# ESP32-WROOM.net
KiCad netlist of a schematic drawn in Altium Designer
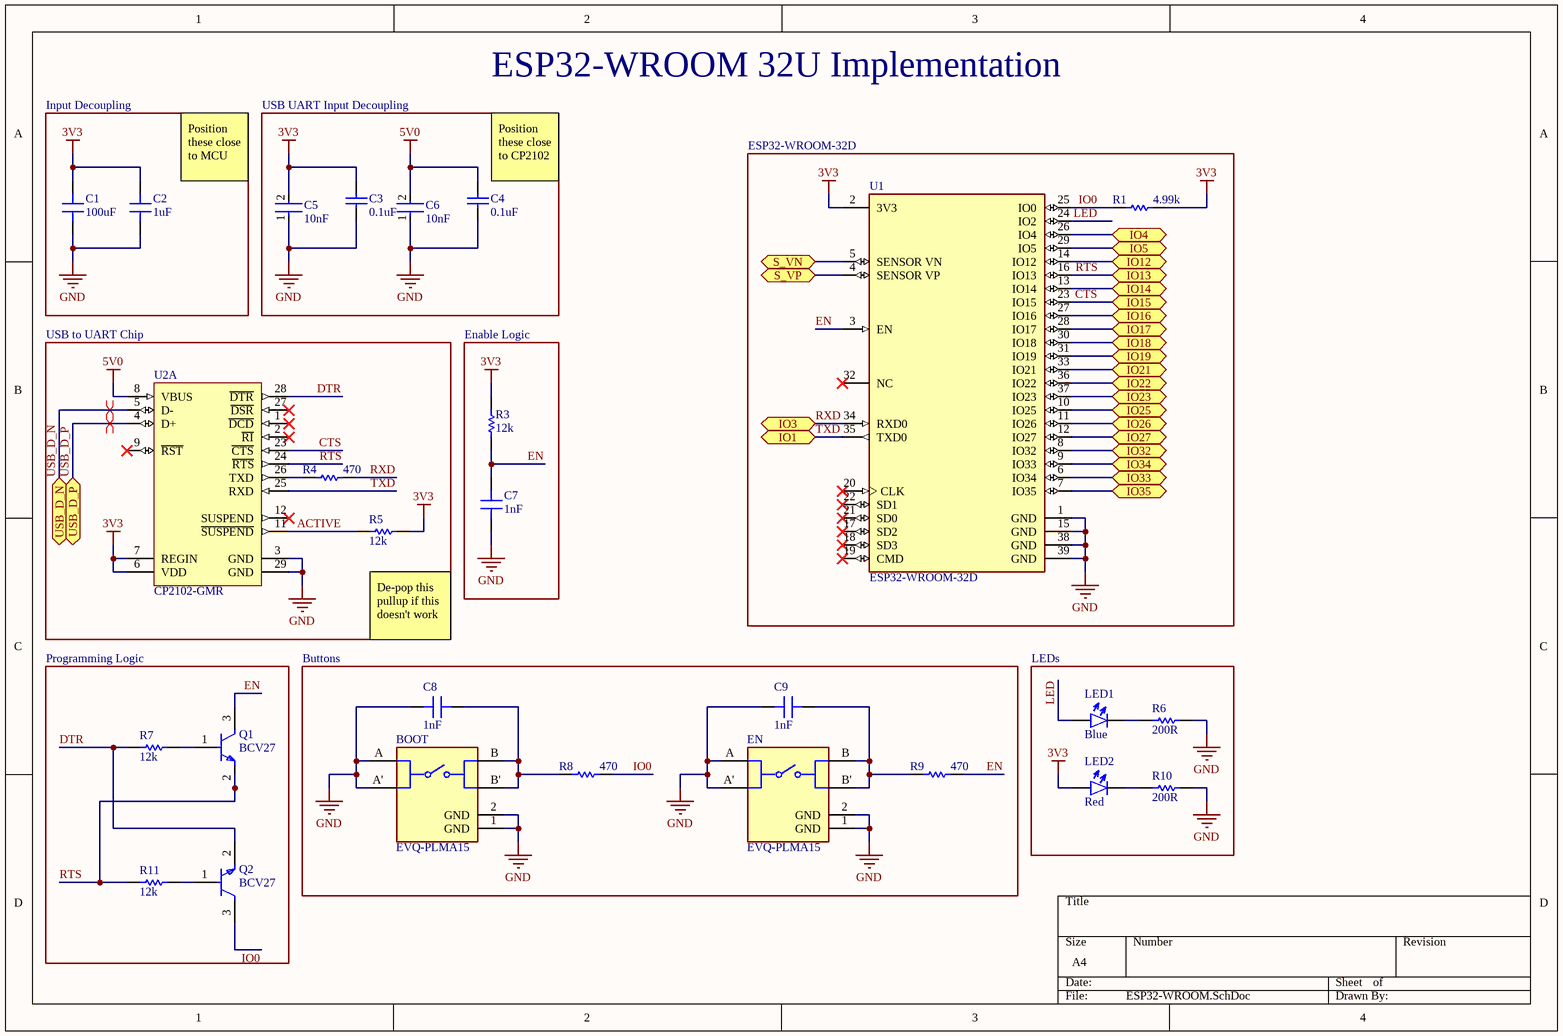
[diagram p0: ESP32-WROOM.SchDoc]

(export (version "E")
  (design (tool "Eeschema 10.0.6"))
  (components
    (comp (ref "BOOT")
      (value "EVQ-PLMA15")
      (footprint "FP-EVQ-PLMA15-MFG")
      (description "SWITCH TACTILE SPST-NO 0.02A 15V")
      (fields
        (field (name "OCTOPART") "https://octopart.com/evq-plma15-panasonic-39850235")
        (field (name "MANUFACTURER") "Panasonic Electronic Components")
      )
      (libsource (lib "Altium Content Vault") (part "fc7b47d2e4813f0909612a6c4f63938"))
    )
    (comp (ref "C1")
      (value "100uF")
      (footprint "0805")
      (fields
        (field (name "MANUFACTURER") "Murata")
        (field (name "MANUFACTURER PART NUMBER") "GRM31CR60J107ME39L")
        (field (name "TOLERANCE") "20%")
      )
      (libsource (lib "Dummy Parts") (part "Capacitor - Ceramic"))
    )
    (comp (ref "C2")
      (value "1uF")
      (footprint "0805")
      (description "SAMSUNG ELECTRO-MECHANICS - CL21B105KOFNNNE - CERAMIC MULTILAYER MLCC CAPACITORS- SMD")
      (fields
        (field (name "MANUFACTURER") "Samsung")
        (field (name "MANUFACTURER PART NUMBER") "CL21B105KOFNNNE")
      )
      (libsource (lib "Dummy Parts") (part "Capacitor - Ceramic"))
    )
    (comp (ref "C3")
      (value "0.1uF")
      (footprint "CAPC2013X88X50NL20T25")
      (fields
        (field (name "PART NUMBER") "C0805C104K5RACTU")
        (field (name "MANUFACTURER") "Kemet")
        (field (name "TOLERANCE") "10%")
      )
      (libsource (lib "Altium Content Vault") (part "CAP"))
    )
    (comp (ref "C4")
      (value "0.1uF")
      (footprint "CAPC2013X88X50NL20T25")
      (fields
        (field (name "PART NUMBER") "C0805C104K5RACTU")
        (field (name "MANUFACTURER") "Kemet")
        (field (name "TOLERANCE") "10%")
      )
      (libsource (lib "Altium Content Vault") (part "CAP"))
    )
    (comp (ref "C5")
      (value "10nF")
      (footprint "FP-CL21-IPC_A")
      (description "CL21 Series 0805 10nF 100V ±10% Tolerance X7R Multilayer Ceramic Chip Capacitor")
      (fields (field (name "VOLTAGE") "100V") (field (name "TOLERANCE") "10%"))
      (libsource (lib "Altium Content Vault") (part "b4654b650e69147ec39a6b967a45e02"))
    )
    (comp (ref "C6")
      (value "10nF")
      (footprint "FP-CL21-IPC_A")
      (description "CL21 Series 0805 10nF 100V ±10% Tolerance X7R Multilayer Ceramic Chip Capacitor")
      (fields (field (name "VOLTAGE") "100V") (field (name "TOLERANCE") "10%"))
      (libsource (lib "Altium Content Vault") (part "b4654b650e69147ec39a6b967a45e02"))
    )
    (comp (ref "C7")
      (value "1nF")
      (footprint "0805")
      (fields
        (field (name "MANUFACTURER") "Samsung")
        (field (name "MANUFACTURER PART NUMBER") "CL21B102KCANNNC")
        (field (name "TOLERANCE") "10%")
      )
      (libsource (lib "Dummy Parts") (part "Capacitor - Ceramic"))
    )
    (comp (ref "C8")
      (value "1nF")
      (footprint "0805")
      (fields
        (field (name "MANUFACTURER") "Samsung")
        (field (name "MANUFACTURER PART NUMBER") "CL21B102KCANNNC")
        (field (name "TOLERANCE") "10%")
      )
      (libsource (lib "Dummy Parts") (part "Capacitor - Ceramic"))
    )
    (comp (ref "C9")
      (value "1nF")
      (footprint "0805")
      (fields
        (field (name "MANUFACTURER") "Samsung")
        (field (name "MANUFACTURER PART NUMBER") "CL21B102KCANNNC")
        (field (name "TOLERANCE") "10%")
      )
      (libsource (lib "Dummy Parts") (part "Capacitor - Ceramic"))
    )
    (comp (ref "EN")
      (value "EVQ-PLMA15")
      (footprint "FP-EVQ-PLMA15-MFG")
      (description "SWITCH TACTILE SPST-NO 0.02A 15V")
      (fields
        (field (name "OCTOPART") "https://octopart.com/evq-plma15-panasonic-39850235")
        (field (name "MANUFACTURER") "Panasonic Electronic Components")
      )
      (libsource (lib "Altium Content Vault") (part "fc7b47d2e4813f0909612a6c4f63938"))
    )
    (comp (ref "LED1") (value "Blue") (footprint "0805") (libsource (lib "Dummy Parts") (part "LED")))
    (comp (ref "LED2") (value "Red") (footprint "0805") (libsource (lib "Dummy Parts") (part "LED")))
    (comp (ref "Q1")
      (value "BCV27")
      (footprint "FP-318-08-MFG")
      (description "TRANS NPN DARL 30V 1.2A SOT23")
      (fields (field (name "MANUFACTURER") "ON Semiconductor / Fairchild"))
      (libsource (lib "Altium Content Vault") (part "b44e953556f554d0102664c7d152cb4"))
    )
    (comp (ref "Q2")
      (value "BCV27")
      (footprint "FP-318-08-MFG")
      (description "TRANS NPN DARL 30V 1.2A SOT23")
      (fields (field (name "MANUFACTURER") "ON Semiconductor / Fairchild"))
      (libsource (lib "Altium Content Vault") (part "b44e953556f554d0102664c7d152cb4"))
    )
    (comp (ref "R1")
      (value "4.99k")
      (footprint "0805")
      (description "Res Thick Film 2.0 x 1.2 mm 4.99K Ohm 1% 0.125W(1/8W) 100ppm/ C Molded SMD Punched Carrier T/R")
      (fields
        (field (name "MANUFACTURER") "Panasonic")
        (field (name "MANUFACTURER PART NUMBER") "ERJ6ENF4991V")
      )
      (libsource (lib "Dummy Parts") (part "Resistor"))
    )
    (comp (ref "R3")
      (value "12k")
      (footprint "0805")
      (description "Res Thick Film 0805 12K Ohm 1% 1/8W 100ppm/C Molded SMD SMD Paper Tape on Plastic Reel")
      (fields
        (field (name "MANUFACTURER") "Bourns")
        (field (name "MANUFACTURER PART NUMBER") "CR0805-FX-1202ELF")
      )
      (libsource (lib "Dummy Parts") (part "Resistor"))
    )
    (comp (ref "R4")
      (value "470")
      (footprint "0805")
      (description "PANASONIC - ERJ6ENF4700V - RES, 470R, 1%, 0.125W, 0805, THICK FILM")
      (fields
        (field (name "MANUFACTURER") "Panasonic")
        (field (name "MANUFACTURER PART NUMBER") "ERJ-6ENF4700V")
      )
      (libsource (lib "Dummy Parts") (part "Resistor"))
    )
    (comp (ref "R5")
      (value "12k")
      (footprint "0805")
      (description "Res Thick Film 0805 12K Ohm 1% 1/8W 100ppm/C Molded SMD SMD Paper Tape on Plastic Reel")
      (fields
        (field (name "MANUFACTURER") "Bourns")
        (field (name "MANUFACTURER PART NUMBER") "CR0805-FX-1202ELF")
      )
      (libsource (lib "Dummy Parts") (part "Resistor"))
    )
    (comp (ref "R6")
      (value "200R")
      (footprint "0805")
      (description "Resistor; Thick Film; Res 200 Ohms; Pwr-Rtg 0.125 W; Tol 1%; SMT; 0805; Cut Tape")
      (fields
        (field (name "MANUFACTURER") "Panasonic")
        (field (name "MANUFACTURER PART NUMBER") "ERJ-6ENF2000V")
      )
      (libsource (lib "Dummy Parts") (part "Resistor"))
    )
    (comp (ref "R7")
      (value "12k")
      (footprint "0805")
      (description "Res Thick Film 0805 12K Ohm 1% 1/8W 100ppm/C Molded SMD SMD Paper Tape on Plastic Reel")
      (fields
        (field (name "MANUFACTURER") "Bourns")
        (field (name "MANUFACTURER PART NUMBER") "CR0805-FX-1202ELF")
      )
      (libsource (lib "Dummy Parts") (part "Resistor"))
    )
    (comp (ref "R8")
      (value "470")
      (footprint "0805")
      (description "PANASONIC - ERJ6ENF4700V - RES, 470R, 1%, 0.125W, 0805, THICK FILM")
      (fields
        (field (name "MANUFACTURER") "Panasonic")
        (field (name "MANUFACTURER PART NUMBER") "ERJ-6ENF4700V")
      )
      (libsource (lib "Dummy Parts") (part "Resistor"))
    )
    (comp (ref "R9")
      (value "470")
      (footprint "0805")
      (description "PANASONIC - ERJ6ENF4700V - RES, 470R, 1%, 0.125W, 0805, THICK FILM")
      (fields
        (field (name "MANUFACTURER") "Panasonic")
        (field (name "MANUFACTURER PART NUMBER") "ERJ-6ENF4700V")
      )
      (libsource (lib "Dummy Parts") (part "Resistor"))
    )
    (comp (ref "R10")
      (value "200R")
      (footprint "0805")
      (description "Resistor; Thick Film; Res 200 Ohms; Pwr-Rtg 0.125 W; Tol 1%; SMT; 0805; Cut Tape")
      (fields
        (field (name "MANUFACTURER") "Panasonic")
        (field (name "MANUFACTURER PART NUMBER") "ERJ-6ENF2000V")
      )
      (libsource (lib "Dummy Parts") (part "Resistor"))
    )
    (comp (ref "R11")
      (value "12k")
      (footprint "0805")
      (description "Res Thick Film 0805 12K Ohm 1% 1/8W 100ppm/C Molded SMD SMD Paper Tape on Plastic Reel")
      (fields
        (field (name "MANUFACTURER") "Bourns")
        (field (name "MANUFACTURER PART NUMBER") "CR0805-FX-1202ELF")
      )
      (libsource (lib "Dummy Parts") (part "Resistor"))
    )
    (comp (ref "U1")
      (value "ESP32-WROOM-32D")
      (footprint "FP-ESP32-WROOM-32D-MFG")
      (description "WIFI MODULE 32MBITS SPI FLASH")
      (fields
        (field (name "OCTOPART") "https://octopart.com/esp32-wroom-32d-espressif+systems-91040050")
        (field (name "MANUFACTURER") "Espressif Systems")
      )
      (libsource (lib "Altium Content Vault") (part "a031a76f8c27026a7a7f4657ff233a3"))
    )
    (comp (ref "U2")
      (value "CP2102-GMR")
      (footprint "SLAB-QFN-28-3125x3125TP_M")
      (description "Single-Chip USB to URAT Bridge, 3.3 V, -40 to 85 degC, 28-Pin QFN, RoHS, Tape and Reel")
      (fields (field (name "MANUFACTURER") "Silicon Labs"))
      (libsource (lib "Altium Content Vault") (part "SLAB-CP210X-QFN-28-29"))
    )
  )
  (nets
    (net (code "1") (name "/ACTIVE") (class "Default")
      (node (ref "R5") (pin "1") (pinfunction "1_1") (pintype "passive"))
      (node (ref "U2") (pin "11") (pinfunction "~{SUSPEND}_11") (pintype "output"))
    )
    (net (code "2") (name "/CTS") (class "Default")
      (node (ref "U1") (pin "23") (pinfunction "IO15_23") (pintype "bidirectional"))
      (node (ref "U2") (pin "23") (pinfunction "~{CTS}_23") (pintype "input"))
    )
    (net (code "3") (name "/DTR") (class "Default")
      (node (ref "Q2") (pin "2") (pinfunction "E_2") (pintype "passive"))
      (node (ref "R7") (pin "1") (pinfunction "1_1") (pintype "passive"))
      (node (ref "U2") (pin "28") (pinfunction "~{DTR}_28") (pintype "output"))
    )
    (net (code "4") (name "/EN") (class "Default")
      (node (ref "C7") (pin "2") (pinfunction "2_2") (pintype "passive"))
      (node (ref "Q1") (pin "3") (pinfunction "C_3") (pintype "passive"))
      (node (ref "R3") (pin "1") (pinfunction "1_1") (pintype "passive"))
      (node (ref "R9") (pin "1") (pinfunction "1_1") (pintype "passive"))
      (node (ref "U1") (pin "3") (pinfunction "EN_3") (pintype "input"))
    )
    (net (code "5") (name "/IO0") (class "Default")
      (node (ref "Q2") (pin "3") (pinfunction "C_3") (pintype "passive"))
      (node (ref "R1") (pin "1") (pinfunction "1_1") (pintype "passive"))
      (node (ref "R8") (pin "1") (pinfunction "1_1") (pintype "passive"))
      (node (ref "U1") (pin "25") (pinfunction "IO0_25") (pintype "bidirectional"))
    )
    (net (code "6") (name "/IO4") (class "Default")
      (node (ref "U1") (pin "26") (pinfunction "IO4_26") (pintype "bidirectional"))
    )
    (net (code "7") (name "/IO5") (class "Default")
      (node (ref "U1") (pin "29") (pinfunction "IO5_29") (pintype "bidirectional"))
    )
    (net (code "8") (name "/IO12") (class "Default")
      (node (ref "U1") (pin "14") (pinfunction "IO12_14") (pintype "bidirectional"))
    )
    (net (code "9") (name "/IO14") (class "Default")
      (node (ref "U1") (pin "13") (pinfunction "IO14_13") (pintype "bidirectional"))
    )
    (net (code "10") (name "/IO16") (class "Default")
      (node (ref "U1") (pin "27") (pinfunction "IO16_27") (pintype "bidirectional"))
    )
    (net (code "11") (name "/IO17") (class "Default")
      (node (ref "U1") (pin "28") (pinfunction "IO17_28") (pintype "bidirectional"))
    )
    (net (code "12") (name "/IO18") (class "Default")
      (node (ref "U1") (pin "30") (pinfunction "IO18_30") (pintype "bidirectional"))
    )
    (net (code "13") (name "/IO19") (class "Default")
      (node (ref "U1") (pin "31") (pinfunction "IO19_31") (pintype "bidirectional"))
    )
    (net (code "14") (name "/IO21") (class "Default")
      (node (ref "U1") (pin "33") (pinfunction "IO21_33") (pintype "bidirectional"))
    )
    (net (code "15") (name "/IO22") (class "Default")
      (node (ref "U1") (pin "36") (pinfunction "IO22_36") (pintype "bidirectional"))
    )
    (net (code "16") (name "/IO23") (class "Default")
      (node (ref "U1") (pin "37") (pinfunction "IO23_37") (pintype "bidirectional"))
    )
    (net (code "17") (name "/IO25") (class "Default")
      (node (ref "U1") (pin "10") (pinfunction "IO25_10") (pintype "bidirectional"))
    )
    (net (code "18") (name "/IO26") (class "Default")
      (node (ref "U1") (pin "11") (pinfunction "IO26_11") (pintype "bidirectional"))
    )
    (net (code "19") (name "/IO27") (class "Default")
      (node (ref "U1") (pin "12") (pinfunction "IO27_12") (pintype "bidirectional"))
    )
    (net (code "20") (name "/IO32") (class "Default")
      (node (ref "U1") (pin "8") (pinfunction "IO32_8") (pintype "bidirectional"))
    )
    (net (code "21") (name "/IO33") (class "Default")
      (node (ref "U1") (pin "6") (pinfunction "IO34_6") (pintype "bidirectional"))
    )
    (net (code "22") (name "/IO34") (class "Default")
      (node (ref "U1") (pin "9") (pinfunction "IO33_9") (pintype "bidirectional"))
    )
    (net (code "23") (name "/IO35") (class "Default")
      (node (ref "U1") (pin "7") (pinfunction "IO35_7") (pintype "bidirectional"))
    )
    (net (code "24") (name "/LED") (class "Default")
      (node (ref "LED1") (pin "1") (pinfunction "1_1") (pintype "passive"))
      (node (ref "U1") (pin "24") (pinfunction "IO2_24") (pintype "bidirectional"))
    )
    (net (code "25") (name "/RTS") (class "Default")
      (node (ref "Q1") (pin "2") (pinfunction "E_2") (pintype "passive"))
      (node (ref "R11") (pin "1") (pinfunction "1_1") (pintype "passive"))
      (node (ref "U1") (pin "16") (pinfunction "IO13_16") (pintype "bidirectional"))
      (node (ref "U2") (pin "24") (pinfunction "~{RTS}_24") (pintype "output"))
    )
    (net (code "26") (name "/RXD") (class "Default")
      (node (ref "R4") (pin "1") (pinfunction "1_1") (pintype "passive"))
      (node (ref "U1") (pin "34") (pinfunction "RXD0_34") (pintype "input"))
    )
    (net (code "27") (name "/S_VN") (class "Default")
      (node (ref "U1") (pin "5") (pinfunction "SENSOR_VN_5") (pintype "bidirectional"))
    )
    (net (code "28") (name "/S_VP") (class "Default")
      (node (ref "U1") (pin "4") (pinfunction "SENSOR_VP_4") (pintype "bidirectional"))
    )
    (net (code "29") (name "/TXD") (class "Default")
      (node (ref "U1") (pin "35") (pinfunction "TXD0_35") (pintype "output"))
      (node (ref "U2") (pin "25") (pinfunction "RXD_25") (pintype "input"))
    )
    (net (code "30") (name "/USB_D_N") (class "Default")
      (node (ref "U2") (pin "5") (pinfunction "D-_5") (pintype "bidirectional"))
    )
    (net (code "31") (name "/USB_D_P") (class "Default")
      (node (ref "U2") (pin "4") (pinfunction "D+_4") (pintype "bidirectional"))
    )
    (net (code "32") (name "3V3") (class "Default")
      (node (ref "C1") (pin "2") (pinfunction "2_2") (pintype "passive"))
      (node (ref "C2") (pin "2") (pinfunction "2_2") (pintype "passive"))
      (node (ref "C3") (pin "2") (pinfunction "2_2") (pintype "passive"))
      (node (ref "C5") (pin "2") (pinfunction "2_2") (pintype "passive"))
      (node (ref "LED2") (pin "1") (pinfunction "1_1") (pintype "passive"))
      (node (ref "R1") (pin "2") (pinfunction "2_2") (pintype "passive"))
      (node (ref "R3") (pin "2") (pinfunction "2_2") (pintype "passive"))
      (node (ref "R5") (pin "2") (pinfunction "2_2") (pintype "passive"))
      (node (ref "U1") (pin "2") (pinfunction "3V3_2") (pintype "power_in"))
      (node (ref "U2") (pin "6") (pinfunction "VDD_6") (pintype "power_in"))
      (node (ref "U2") (pin "7") (pinfunction "REGIN_7") (pintype "power_in"))
    )
    (net (code "33") (name "5V0") (class "Default")
      (node (ref "C4") (pin "2") (pinfunction "2_2") (pintype "passive"))
      (node (ref "C6") (pin "2") (pinfunction "2_2") (pintype "passive"))
      (node (ref "U2") (pin "8") (pinfunction "VBUS_8") (pintype "input"))
    )
    (net (code "34") (name "GND") (class "Default")
      (node (ref "BOOT") (pin "1") (pinfunction "GND_1") (pintype "power_in"))
      (node (ref "BOOT") (pin "2") (pinfunction "GND_2") (pintype "power_in"))
      (node (ref "BOOT") (pin "A") (pinfunction "A_A") (pintype "passive"))
      (node (ref "BOOT") (pin "A'") (pinfunction "A'_A'") (pintype "passive"))
      (node (ref "C1") (pin "1") (pinfunction "1_1") (pintype "passive"))
      (node (ref "C2") (pin "1") (pinfunction "1_1") (pintype "passive"))
      (node (ref "C3") (pin "1") (pinfunction "1_1") (pintype "passive"))
      (node (ref "C4") (pin "1") (pinfunction "1_1") (pintype "passive"))
      (node (ref "C5") (pin "1") (pinfunction "1_1") (pintype "passive"))
      (node (ref "C6") (pin "1") (pinfunction "1_1") (pintype "passive"))
      (node (ref "C7") (pin "1") (pinfunction "1_1") (pintype "passive"))
      (node (ref "C8") (pin "1") (pinfunction "1_1") (pintype "passive"))
      (node (ref "C9") (pin "1") (pinfunction "1_1") (pintype "passive"))
      (node (ref "EN") (pin "1") (pinfunction "GND_1") (pintype "power_in"))
      (node (ref "EN") (pin "2") (pinfunction "GND_2") (pintype "power_in"))
      (node (ref "EN") (pin "A") (pinfunction "A_A") (pintype "passive"))
      (node (ref "EN") (pin "A'") (pinfunction "A'_A'") (pintype "passive"))
      (node (ref "R10") (pin "2") (pinfunction "2_2") (pintype "passive"))
      (node (ref "R6") (pin "2") (pinfunction "2_2") (pintype "passive"))
      (node (ref "U1") (pin "1") (pinfunction "GND_1") (pintype "power_in"))
      (node (ref "U1") (pin "15") (pinfunction "GND_15") (pintype "power_in"))
      (node (ref "U1") (pin "38") (pinfunction "GND_38") (pintype "power_in"))
      (node (ref "U1") (pin "39") (pinfunction "GND_39") (pintype "power_in"))
      (node (ref "U2") (pin "29") (pinfunction "GND_29") (pintype "power_in"))
      (node (ref "U2") (pin "3") (pinfunction "GND_3") (pintype "power_in"))
    )
    (net (code "35") (name "Net-(BOOT-PadB')") (class "Default")
      (node (ref "BOOT") (pin "B") (pinfunction "B_B") (pintype "passive"))
      (node (ref "BOOT") (pin "B'") (pinfunction "B'_B'") (pintype "passive"))
      (node (ref "C8") (pin "2") (pinfunction "2_2") (pintype "passive"))
      (node (ref "R8") (pin "2") (pinfunction "2_2") (pintype "passive"))
    )
    (net (code "36") (name "Net-(C9-Pad2)") (class "Default")
      (node (ref "C9") (pin "2") (pinfunction "2_2") (pintype "passive"))
      (node (ref "EN") (pin "B") (pinfunction "B_B") (pintype "passive"))
      (node (ref "EN") (pin "B'") (pinfunction "B'_B'") (pintype "passive"))
      (node (ref "R9") (pin "2") (pinfunction "2_2") (pintype "passive"))
    )
    (net (code "37") (name "Net-(LED1-Pad2)") (class "Default")
      (node (ref "LED1") (pin "2") (pinfunction "2_2") (pintype "passive"))
      (node (ref "R6") (pin "1") (pinfunction "1_1") (pintype "passive"))
    )
    (net (code "38") (name "Net-(LED2-Pad2)") (class "Default")
      (node (ref "LED2") (pin "2") (pinfunction "2_2") (pintype "passive"))
      (node (ref "R10") (pin "1") (pinfunction "1_1") (pintype "passive"))
    )
    (net (code "39") (name "Net-(Q1-B)") (class "Default")
      (node (ref "Q1") (pin "1") (pinfunction "B_1") (pintype "passive"))
      (node (ref "R7") (pin "2") (pinfunction "2_2") (pintype "passive"))
    )
    (net (code "40") (name "Net-(Q2-B)") (class "Default")
      (node (ref "Q2") (pin "1") (pinfunction "B_1") (pintype "passive"))
      (node (ref "R11") (pin "2") (pinfunction "2_2") (pintype "passive"))
    )
    (net (code "41") (name "Net-(U2A-TXD)") (class "Default")
      (node (ref "R4") (pin "2") (pinfunction "2_2") (pintype "passive"))
      (node (ref "U2") (pin "26") (pinfunction "TXD_26") (pintype "output"))
    )
    (net (code "42") (name "unconnected-(U1-CLK-Pad20)") (class "Default")
      (node (ref "U1") (pin "20") (pinfunction "CLK_20") (pintype "input+no_connect"))
    )
    (net (code "43") (name "unconnected-(U1-CMD-Pad19)") (class "Default")
      (node (ref "U1") (pin "19") (pinfunction "CMD_19") (pintype "bidirectional+no_connect"))
    )
    (net (code "44") (name "unconnected-(U1-NC-Pad32)") (class "Default")
      (node (ref "U1") (pin "32") (pinfunction "NC_32") (pintype "passive+no_connect"))
    )
    (net (code "45") (name "unconnected-(U1-SD0-Pad21)") (class "Default")
      (node (ref "U1") (pin "21") (pinfunction "SD0_21") (pintype "bidirectional+no_connect"))
    )
    (net (code "46") (name "unconnected-(U1-SD1-Pad22)") (class "Default")
      (node (ref "U1") (pin "22") (pinfunction "SD1_22") (pintype "bidirectional+no_connect"))
    )
    (net (code "47") (name "unconnected-(U1-SD2-Pad17)") (class "Default")
      (node (ref "U1") (pin "17") (pinfunction "SD2_17") (pintype "bidirectional+no_connect"))
    )
    (net (code "48") (name "unconnected-(U1-SD3-Pad18)") (class "Default")
      (node (ref "U1") (pin "18") (pinfunction "SD3_18") (pintype "bidirectional+no_connect"))
    )
    (net (code "49") (name "unconnected-(U2A-SUSPEND-Pad12)") (class "Default")
      (node (ref "U2") (pin "12") (pinfunction "SUSPEND_12") (pintype "output+no_connect"))
    )
    (net (code "50") (name "unconnected-(U2A-~{DCD}-Pad1)") (class "Default")
      (node (ref "U2") (pin "1") (pinfunction "~{DCD}_1") (pintype "input+no_connect"))
    )
    (net (code "51") (name "unconnected-(U2A-~{DSR}-Pad27)") (class "Default")
      (node (ref "U2") (pin "27") (pinfunction "~{DSR}_27") (pintype "input+no_connect"))
    )
    (net (code "52") (name "unconnected-(U2A-~{RI}-Pad2)") (class "Default")
      (node (ref "U2") (pin "2") (pinfunction "~{RI}_2") (pintype "input+no_connect"))
    )
    (net (code "53") (name "unconnected-(U2A-~{RST}-Pad9)") (class "Default")
      (node (ref "U2") (pin "9") (pinfunction "~{RST}_9") (pintype "bidirectional+no_connect"))
    )
  )
)
